# Adafruit_VL53L0X.net
KiCad netlist of a schematic drawn in EAGLE
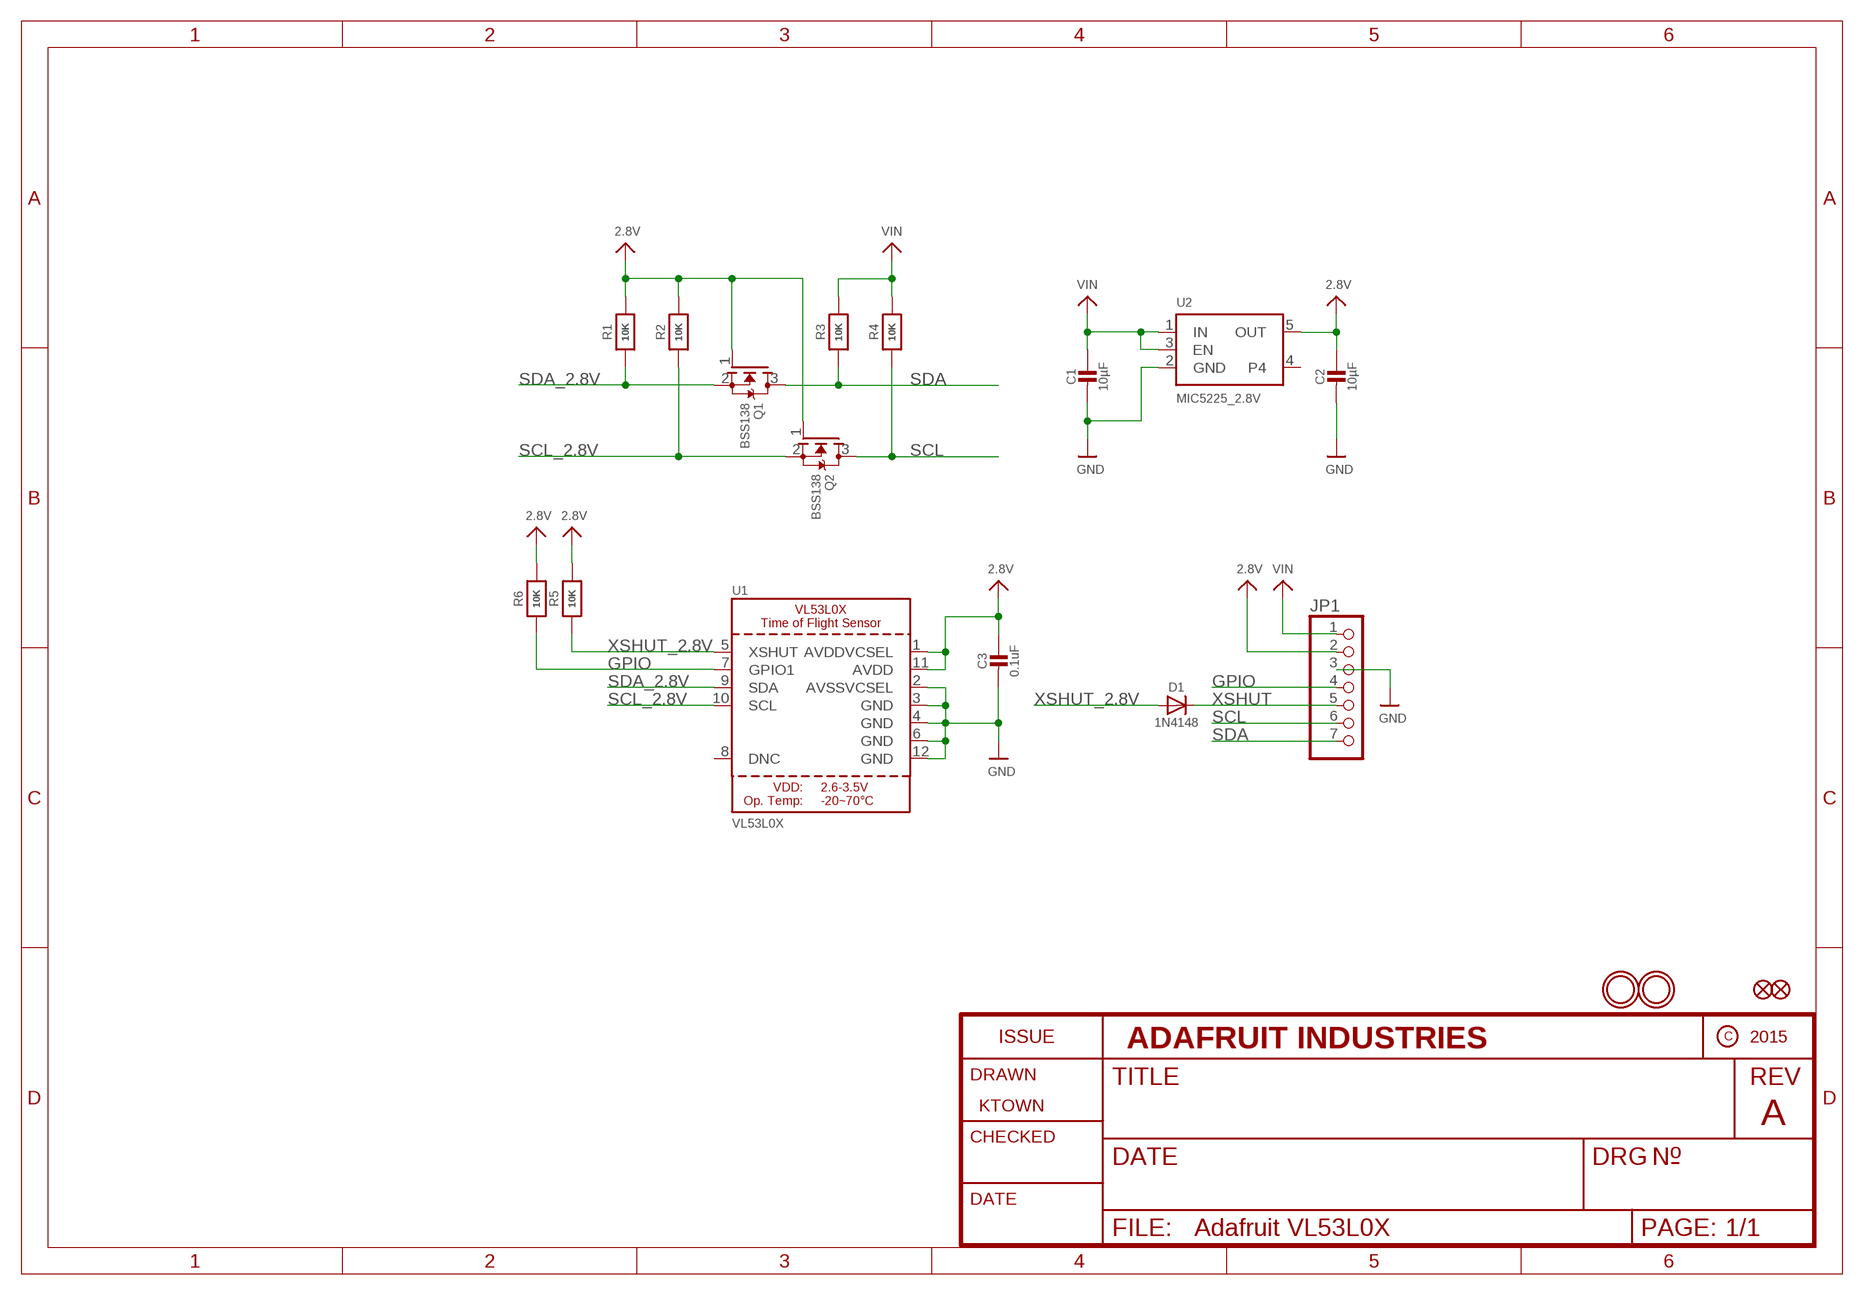
[diagram p0: schematic, sheet 1]

(export (version "E")
  (design (tool "Eeschema 10.0.6"))
  (components
    (comp (ref "C1")
      (value "10µF")
      (footprint "eagle-import:0805-NO")
      (libsource (lib "eagle-import") (part "CAP_CERAMIC0805-NOOUTLINE"))
    )
    (comp (ref "C2")
      (value "10µF")
      (footprint "eagle-import:0805-NO")
      (libsource (lib "eagle-import") (part "CAP_CERAMIC0805-NOOUTLINE"))
    )
    (comp (ref "C3")
      (value "0.1uF")
      (footprint "eagle-import:0805-NO")
      (libsource (lib "eagle-import") (part "CAP_CERAMIC0805-NOOUTLINE"))
    )
    (comp (ref "D1")
      (value "1N4148")
      (footprint "eagle-import:SOD-323")
      (libsource (lib "eagle-import") (part "DIODESOD-323"))
    )
    (comp (ref "FID2")
      (value "FIDUCIAL\"\"")
      (footprint "eagle-import:FIDUCIAL_1MM")
      (libsource (lib "eagle-import") (part "FIDUCIAL{dblquote}{dblquote}"))
    )
    (comp (ref "FID3")
      (value "FIDUCIAL\"\"")
      (footprint "eagle-import:FIDUCIAL_1MM")
      (libsource (lib "eagle-import") (part "FIDUCIAL{dblquote}{dblquote}"))
    )
    (comp (ref "JP1")
      (value "HEADER-1X770MIL")
      (footprint "eagle-import:1X07_ROUND_70")
      (libsource (lib "eagle-import") (part "HEADER-1X770MIL"))
    )
    (comp (ref "Q1")
      (value "BSS138")
      (footprint "eagle-import:SOT23-WIDE")
      (libsource (lib "eagle-import") (part "MOSFET-NWIDE"))
    )
    (comp (ref "Q2")
      (value "BSS138")
      (footprint "eagle-import:SOT23-WIDE")
      (libsource (lib "eagle-import") (part "MOSFET-NWIDE"))
    )
    (comp (ref "R1")
      (value "10K")
      (footprint "eagle-import:0805-NO")
      (libsource (lib "eagle-import") (part "RESISTOR0805_NOOUTLINE"))
    )
    (comp (ref "R2")
      (value "10K")
      (footprint "eagle-import:0805-NO")
      (libsource (lib "eagle-import") (part "RESISTOR0805_NOOUTLINE"))
    )
    (comp (ref "R3")
      (value "10K")
      (footprint "eagle-import:0805-NO")
      (libsource (lib "eagle-import") (part "RESISTOR0805_NOOUTLINE"))
    )
    (comp (ref "R4")
      (value "10K")
      (footprint "eagle-import:0805-NO")
      (libsource (lib "eagle-import") (part "RESISTOR0805_NOOUTLINE"))
    )
    (comp (ref "R5")
      (value "10K")
      (footprint "eagle-import:0805-NO")
      (libsource (lib "eagle-import") (part "RESISTOR0805_NOOUTLINE"))
    )
    (comp (ref "R6")
      (value "10K")
      (footprint "eagle-import:0805-NO")
      (libsource (lib "eagle-import") (part "RESISTOR0805_NOOUTLINE"))
    )
    (comp (ref "U$13")
      (value "MOUNTINGHOLE2.5")
      (footprint "eagle-import:MOUNTINGHOLE_2.5_PLATED")
      (libsource (lib "eagle-import") (part "MOUNTINGHOLE2.5"))
    )
    (comp (ref "U$14")
      (value "MOUNTINGHOLE2.5")
      (footprint "eagle-import:MOUNTINGHOLE_2.5_PLATED")
      (libsource (lib "eagle-import") (part "MOUNTINGHOLE2.5"))
    )
    (comp (ref "U1")
      (value "VL53L0X")
      (footprint "eagle-import:LGA12_ST")
      (libsource (lib "eagle-import") (part "VL53L0X"))
    )
    (comp (ref "U2")
      (value "MIC5225_2.8V")
      (footprint "eagle-import:SOT23-5")
      (libsource (lib "eagle-import") (part "VREG_SOT23-5"))
    )
  )
  (nets
    (net (code "1") (name "/GPIO") (class "Default")
      (node (ref "JP1") (pin "4") (pinfunction "4_4") (pintype "passive"))
      (node (ref "R6") (pin "1") (pinfunction "1_1") (pintype "passive"))
      (node (ref "U1") (pin "7") (pinfunction "GPIO1_7") (pintype "output"))
    )
    (net (code "2") (name "/SCL") (class "Default")
      (node (ref "JP1") (pin "6") (pinfunction "6_6") (pintype "passive"))
      (node (ref "Q2") (pin "3") (pinfunction "D_3") (pintype "bidirectional"))
      (node (ref "R4") (pin "1") (pinfunction "1_1") (pintype "passive"))
    )
    (net (code "3") (name "/SCL_2.8V") (class "Default")
      (node (ref "Q2") (pin "2") (pinfunction "S_2") (pintype "bidirectional"))
      (node (ref "R2") (pin "1") (pinfunction "1_1") (pintype "passive"))
      (node (ref "U1") (pin "10") (pinfunction "SCL_10") (pintype "open_collector"))
    )
    (net (code "4") (name "/SDA") (class "Default")
      (node (ref "JP1") (pin "7") (pinfunction "7_7") (pintype "passive"))
      (node (ref "Q1") (pin "3") (pinfunction "D_3") (pintype "bidirectional"))
      (node (ref "R3") (pin "1") (pinfunction "1_1") (pintype "passive"))
    )
    (net (code "5") (name "/SDA_2.8V") (class "Default")
      (node (ref "Q1") (pin "2") (pinfunction "S_2") (pintype "bidirectional"))
      (node (ref "R1") (pin "1") (pinfunction "1_1") (pintype "passive"))
      (node (ref "U1") (pin "9") (pinfunction "SDA_9") (pintype "open_collector"))
    )
    (net (code "6") (name "/XSHUT") (class "Default")
      (node (ref "D1") (pin "C") (pinfunction "C_C") (pintype "passive"))
      (node (ref "JP1") (pin "5") (pinfunction "5_5") (pintype "passive"))
    )
    (net (code "7") (name "/XSHUT_2.8V") (class "Default")
      (node (ref "D1") (pin "A") (pinfunction "A_A") (pintype "passive"))
      (node (ref "R5") (pin "1") (pinfunction "1_1") (pintype "passive"))
      (node (ref "U1") (pin "5") (pinfunction "XSHUT_5") (pintype "input"))
    )
    (net (code "8") (name "2.8V") (class "Default")
      (node (ref "C2") (pin "1") (pinfunction "1_1") (pintype "passive"))
      (node (ref "C3") (pin "1") (pinfunction "1_1") (pintype "passive"))
      (node (ref "JP1") (pin "2") (pinfunction "2_2") (pintype "passive"))
      (node (ref "Q1") (pin "1") (pinfunction "G_1") (pintype "bidirectional"))
      (node (ref "Q2") (pin "1") (pinfunction "G_1") (pintype "bidirectional"))
      (node (ref "R1") (pin "2") (pinfunction "2_2") (pintype "passive"))
      (node (ref "R2") (pin "2") (pinfunction "2_2") (pintype "passive"))
      (node (ref "R5") (pin "2") (pinfunction "2_2") (pintype "passive"))
      (node (ref "R6") (pin "2") (pinfunction "2_2") (pintype "passive"))
      (node (ref "U1") (pin "1") (pinfunction "AVDDVCSEL_1") (pintype "power_in"))
      (node (ref "U1") (pin "11") (pinfunction "AVDD_11") (pintype "power_in"))
      (node (ref "U2") (pin "5") (pinfunction "OUT_5") (pintype "power_in"))
    )
    (net (code "9") (name "GND") (class "Default")
      (node (ref "C1") (pin "2") (pinfunction "2_2") (pintype "passive"))
      (node (ref "C2") (pin "2") (pinfunction "2_2") (pintype "passive"))
      (node (ref "C3") (pin "2") (pinfunction "2_2") (pintype "passive"))
      (node (ref "JP1") (pin "3") (pinfunction "3_3") (pintype "passive"))
      (node (ref "U1") (pin "12") (pinfunction "GND_12") (pintype "power_in"))
      (node (ref "U1") (pin "2") (pinfunction "AVSSVCSEL_2") (pintype "power_in"))
      (node (ref "U1") (pin "3") (pinfunction "GND_3") (pintype "power_in"))
      (node (ref "U1") (pin "4") (pinfunction "GND_4") (pintype "power_in"))
      (node (ref "U1") (pin "6") (pinfunction "GND_6") (pintype "power_in"))
      (node (ref "U2") (pin "2") (pinfunction "GND_2") (pintype "power_in"))
    )
    (net (code "10") (name "VIN") (class "Default")
      (node (ref "C1") (pin "1") (pinfunction "1_1") (pintype "passive"))
      (node (ref "JP1") (pin "1") (pinfunction "1_1") (pintype "passive"))
      (node (ref "R3") (pin "2") (pinfunction "2_2") (pintype "passive"))
      (node (ref "R4") (pin "2") (pinfunction "2_2") (pintype "passive"))
      (node (ref "U2") (pin "1") (pinfunction "IN_1") (pintype "power_in"))
      (node (ref "U2") (pin "3") (pinfunction "EN_3") (pintype "input"))
    )
    (net (code "11") (name "unconnected-(U1-DNC-Pad8)") (class "Default")
      (node (ref "U1") (pin "8") (pinfunction "DNC_8") (pintype "no_connect"))
    )
    (net (code "12") (name "unconnected-(U2-P4-Pad4)") (class "Default")
      (node (ref "U2") (pin "4") (pinfunction "P4_4") (pintype "bidirectional"))
    )
  )
)
